# BarGraph.net
KiCad netlist of a schematic drawn in Altium Designer
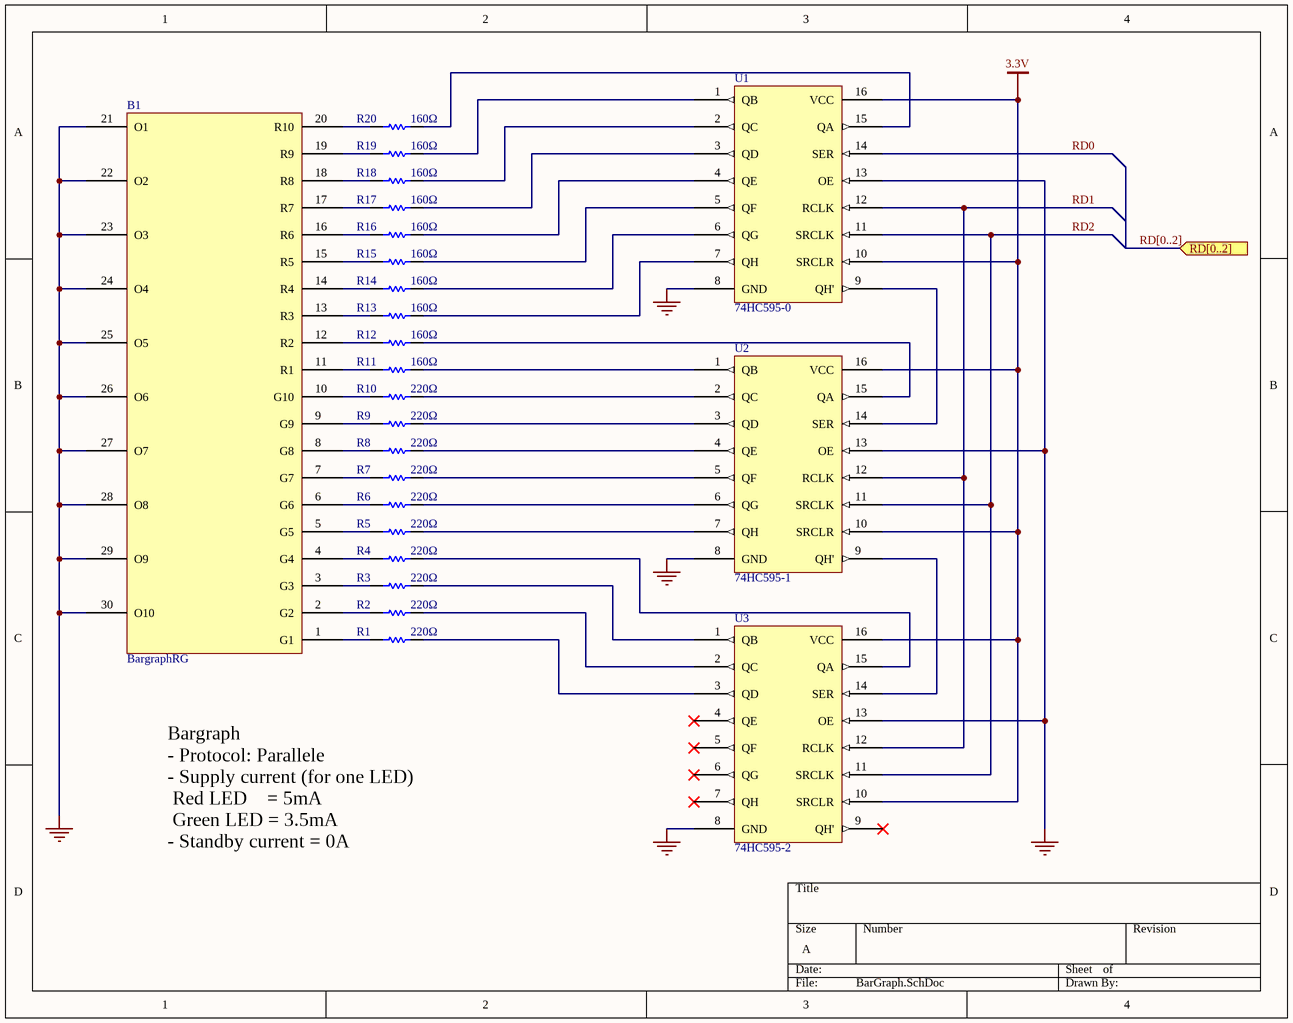
[diagram p0: BarGraph.SchDoc]

(export (version "E")
  (design (tool "Eeschema 10.0.6"))
  (components
    (comp (ref "B1")
      (value "BargraphRG")
      (footprint "BargraphRG")
      (description "Bargraph")
      (fields (field (name "MANUFACTURER") "KINGBRIGHT"))
      (libsource (lib "Electroplant") (part "BargraphRG"))
    )
    (comp (ref "R1")
      (value "220Ω")
      (footprint "R0603")
      (description "Resistor")
      (fields (field (name "PUBLISHER") "Altium Limited"))
      (libsource (lib "Miscellaneous Devices") (part "Res1"))
    )
    (comp (ref "R2")
      (value "220Ω")
      (footprint "R0603")
      (description "Resistor")
      (fields (field (name "PUBLISHER") "Altium Limited"))
      (libsource (lib "Miscellaneous Devices") (part "Res1"))
    )
    (comp (ref "R3")
      (value "220Ω")
      (footprint "R0603")
      (description "Resistor")
      (fields (field (name "PUBLISHER") "Altium Limited"))
      (libsource (lib "Miscellaneous Devices") (part "Res1"))
    )
    (comp (ref "R4")
      (value "220Ω")
      (footprint "R0603")
      (description "Resistor")
      (fields (field (name "PUBLISHER") "Altium Limited"))
      (libsource (lib "Miscellaneous Devices") (part "Res1"))
    )
    (comp (ref "R5")
      (value "220Ω")
      (footprint "R0603")
      (description "Resistor")
      (fields (field (name "PUBLISHER") "Altium Limited"))
      (libsource (lib "Miscellaneous Devices") (part "Res1"))
    )
    (comp (ref "R6")
      (value "220Ω")
      (footprint "R0603")
      (description "Resistor")
      (fields (field (name "PUBLISHER") "Altium Limited"))
      (libsource (lib "Miscellaneous Devices") (part "Res1"))
    )
    (comp (ref "R7")
      (value "220Ω")
      (footprint "R0603")
      (description "Resistor")
      (fields (field (name "PUBLISHER") "Altium Limited"))
      (libsource (lib "Miscellaneous Devices") (part "Res1"))
    )
    (comp (ref "R8")
      (value "220Ω")
      (footprint "R0603")
      (description "Resistor")
      (fields (field (name "PUBLISHER") "Altium Limited"))
      (libsource (lib "Miscellaneous Devices") (part "Res1"))
    )
    (comp (ref "R9")
      (value "220Ω")
      (footprint "R0603")
      (description "Resistor")
      (fields (field (name "PUBLISHER") "Altium Limited"))
      (libsource (lib "Miscellaneous Devices") (part "Res1"))
    )
    (comp (ref "R10")
      (value "220Ω")
      (footprint "R0603")
      (description "Resistor")
      (fields (field (name "PUBLISHER") "Altium Limited"))
      (libsource (lib "Miscellaneous Devices") (part "Res1"))
    )
    (comp (ref "R11")
      (value "160Ω")
      (footprint "R0603")
      (description "Resistor")
      (fields (field (name "PUBLISHER") "Altium Limited"))
      (libsource (lib "Miscellaneous Devices") (part "Res1"))
    )
    (comp (ref "R12")
      (value "160Ω")
      (footprint "R0603")
      (description "Resistor")
      (fields (field (name "PUBLISHER") "Altium Limited"))
      (libsource (lib "Miscellaneous Devices") (part "Res1"))
    )
    (comp (ref "R13")
      (value "160Ω")
      (footprint "R0603")
      (description "Resistor")
      (fields (field (name "PUBLISHER") "Altium Limited"))
      (libsource (lib "Miscellaneous Devices") (part "Res1"))
    )
    (comp (ref "R14")
      (value "160Ω")
      (footprint "R0603")
      (description "Resistor")
      (fields (field (name "PUBLISHER") "Altium Limited"))
      (libsource (lib "Miscellaneous Devices") (part "Res1"))
    )
    (comp (ref "R15")
      (value "160Ω")
      (footprint "R0603")
      (description "Resistor")
      (fields (field (name "PUBLISHER") "Altium Limited"))
      (libsource (lib "Miscellaneous Devices") (part "Res1"))
    )
    (comp (ref "R16")
      (value "160Ω")
      (footprint "R0603")
      (description "Resistor")
      (fields (field (name "PUBLISHER") "Altium Limited"))
      (libsource (lib "Miscellaneous Devices") (part "Res1"))
    )
    (comp (ref "R17")
      (value "160Ω")
      (footprint "R0603")
      (description "Resistor")
      (fields (field (name "PUBLISHER") "Altium Limited"))
      (libsource (lib "Miscellaneous Devices") (part "Res1"))
    )
    (comp (ref "R18")
      (value "160Ω")
      (footprint "R0603")
      (description "Resistor")
      (fields (field (name "PUBLISHER") "Altium Limited"))
      (libsource (lib "Miscellaneous Devices") (part "Res1"))
    )
    (comp (ref "R19")
      (value "160Ω")
      (footprint "R0603")
      (description "Resistor")
      (fields (field (name "PUBLISHER") "Altium Limited"))
      (libsource (lib "Miscellaneous Devices") (part "Res1"))
    )
    (comp (ref "R20")
      (value "160Ω")
      (footprint "R0603")
      (description "Resistor")
      (fields (field (name "PUBLISHER") "Altium Limited"))
      (libsource (lib "Miscellaneous Devices") (part "Res1"))
    )
    (comp (ref "U1")
      (value "74HC595-0")
      (footprint "SN74HC595D")
      (description "ShiftRegister")
      (fields (field (name "MANUFACTURER") "TEXAS INSTRUMENTS"))
      (libsource (lib "Electroplant") (part "74HC595"))
    )
    (comp (ref "U2")
      (value "74HC595-1")
      (footprint "SN74HC595D")
      (description "ShiftRegister")
      (fields (field (name "MANUFACTURER") "TEXAS INSTRUMENTS"))
      (libsource (lib "Electroplant") (part "74HC595"))
    )
    (comp (ref "U3")
      (value "74HC595-2")
      (footprint "SN74HC595D")
      (description "ShiftRegister")
      (fields (field (name "MANUFACTURER") "TEXAS INSTRUMENTS"))
      (libsource (lib "Electroplant") (part "74HC595"))
    )
  )
  (nets
    (net (code "1") (name "/RD0") (class "Default")
      (node (ref "U1") (pin "14") (pinfunction "SER_14") (pintype "input"))
    )
    (net (code "2") (name "/RD1") (class "Default")
      (node (ref "U1") (pin "12") (pinfunction "RCLK_12") (pintype "input"))
      (node (ref "U2") (pin "12") (pinfunction "RCLK_12") (pintype "input"))
      (node (ref "U3") (pin "12") (pinfunction "RCLK_12") (pintype "input"))
    )
    (net (code "3") (name "/RD2") (class "Default")
      (node (ref "U1") (pin "11") (pinfunction "SRCLK_11") (pintype "input"))
      (node (ref "U2") (pin "11") (pinfunction "SRCLK_11") (pintype "input"))
      (node (ref "U3") (pin "11") (pinfunction "SRCLK_11") (pintype "input"))
    )
    (net (code "5") (name "3.3V") (class "Default")
      (node (ref "U1") (pin "10") (pinfunction "SRCLR_10") (pintype "input"))
      (node (ref "U1") (pin "16") (pinfunction "VCC_16") (pintype "power_in"))
      (node (ref "U2") (pin "10") (pinfunction "SRCLR_10") (pintype "input"))
      (node (ref "U2") (pin "16") (pinfunction "VCC_16") (pintype "power_in"))
      (node (ref "U3") (pin "10") (pinfunction "SRCLR_10") (pintype "input"))
      (node (ref "U3") (pin "16") (pinfunction "VCC_16") (pintype "power_in"))
    )
    (net (code "6") (name "GND") (class "Default")
      (node (ref "B1") (pin "21") (pinfunction "O1_21") (pintype "power_in"))
      (node (ref "B1") (pin "22") (pinfunction "O2_22") (pintype "power_in"))
      (node (ref "B1") (pin "23") (pinfunction "O3_23") (pintype "power_in"))
      (node (ref "B1") (pin "24") (pinfunction "O4_24") (pintype "power_in"))
      (node (ref "B1") (pin "25") (pinfunction "O5_25") (pintype "power_in"))
      (node (ref "B1") (pin "26") (pinfunction "O6_26") (pintype "power_in"))
      (node (ref "B1") (pin "27") (pinfunction "O7_27") (pintype "power_in"))
      (node (ref "B1") (pin "28") (pinfunction "O8_28") (pintype "power_in"))
      (node (ref "B1") (pin "29") (pinfunction "O9_29") (pintype "power_in"))
      (node (ref "B1") (pin "30") (pinfunction "O10_30") (pintype "power_in"))
      (node (ref "U1") (pin "13") (pinfunction "OE_13") (pintype "input"))
      (node (ref "U1") (pin "8") (pinfunction "GND_8") (pintype "power_in"))
      (node (ref "U2") (pin "13") (pinfunction "OE_13") (pintype "input"))
      (node (ref "U2") (pin "8") (pinfunction "GND_8") (pintype "power_in"))
      (node (ref "U3") (pin "13") (pinfunction "OE_13") (pintype "input"))
      (node (ref "U3") (pin "8") (pinfunction "GND_8") (pintype "power_in"))
    )
    (net (code "7") (name "Net-(B1-G1)") (class "Default")
      (node (ref "B1") (pin "1") (pinfunction "G1_1") (pintype "power_in"))
      (node (ref "R1") (pin "1") (pinfunction "1_1") (pintype "passive"))
    )
    (net (code "8") (name "Net-(B1-G2)") (class "Default")
      (node (ref "B1") (pin "2") (pinfunction "G2_2") (pintype "power_in"))
      (node (ref "R2") (pin "1") (pinfunction "1_1") (pintype "passive"))
    )
    (net (code "9") (name "Net-(B1-G3)") (class "Default")
      (node (ref "B1") (pin "3") (pinfunction "G3_3") (pintype "power_in"))
      (node (ref "R3") (pin "1") (pinfunction "1_1") (pintype "passive"))
    )
    (net (code "10") (name "Net-(B1-G4)") (class "Default")
      (node (ref "B1") (pin "4") (pinfunction "G4_4") (pintype "power_in"))
      (node (ref "R4") (pin "1") (pinfunction "1_1") (pintype "passive"))
    )
    (net (code "11") (name "Net-(B1-G5)") (class "Default")
      (node (ref "B1") (pin "5") (pinfunction "G5_5") (pintype "power_in"))
      (node (ref "R5") (pin "1") (pinfunction "1_1") (pintype "passive"))
    )
    (net (code "12") (name "Net-(B1-G6)") (class "Default")
      (node (ref "B1") (pin "6") (pinfunction "G6_6") (pintype "power_in"))
      (node (ref "R6") (pin "1") (pinfunction "1_1") (pintype "passive"))
    )
    (net (code "13") (name "Net-(B1-G7)") (class "Default")
      (node (ref "B1") (pin "7") (pinfunction "G7_7") (pintype "power_in"))
      (node (ref "R7") (pin "1") (pinfunction "1_1") (pintype "passive"))
    )
    (net (code "14") (name "Net-(B1-G8)") (class "Default")
      (node (ref "B1") (pin "8") (pinfunction "G8_8") (pintype "power_in"))
      (node (ref "R8") (pin "1") (pinfunction "1_1") (pintype "passive"))
    )
    (net (code "15") (name "Net-(B1-G9)") (class "Default")
      (node (ref "B1") (pin "9") (pinfunction "G9_9") (pintype "power_in"))
      (node (ref "R9") (pin "1") (pinfunction "1_1") (pintype "passive"))
    )
    (net (code "16") (name "Net-(B1-G10)") (class "Default")
      (node (ref "B1") (pin "10") (pinfunction "G10_10") (pintype "power_in"))
      (node (ref "R10") (pin "1") (pinfunction "1_1") (pintype "passive"))
    )
    (net (code "17") (name "Net-(B1-R1)") (class "Default")
      (node (ref "B1") (pin "11") (pinfunction "R1_11") (pintype "power_in"))
      (node (ref "R11") (pin "1") (pinfunction "1_1") (pintype "passive"))
    )
    (net (code "18") (name "Net-(B1-R2)") (class "Default")
      (node (ref "B1") (pin "12") (pinfunction "R2_12") (pintype "power_in"))
      (node (ref "R12") (pin "1") (pinfunction "1_1") (pintype "passive"))
    )
    (net (code "19") (name "Net-(B1-R3)") (class "Default")
      (node (ref "B1") (pin "13") (pinfunction "R3_13") (pintype "power_in"))
      (node (ref "R13") (pin "1") (pinfunction "1_1") (pintype "passive"))
    )
    (net (code "20") (name "Net-(B1-R4)") (class "Default")
      (node (ref "B1") (pin "14") (pinfunction "R4_14") (pintype "power_in"))
      (node (ref "R14") (pin "1") (pinfunction "1_1") (pintype "passive"))
    )
    (net (code "21") (name "Net-(B1-R5)") (class "Default")
      (node (ref "B1") (pin "15") (pinfunction "R5_15") (pintype "power_in"))
      (node (ref "R15") (pin "1") (pinfunction "1_1") (pintype "passive"))
    )
    (net (code "22") (name "Net-(B1-R6)") (class "Default")
      (node (ref "B1") (pin "16") (pinfunction "R6_16") (pintype "power_in"))
      (node (ref "R16") (pin "1") (pinfunction "1_1") (pintype "passive"))
    )
    (net (code "23") (name "Net-(B1-R7)") (class "Default")
      (node (ref "B1") (pin "17") (pinfunction "R7_17") (pintype "power_in"))
      (node (ref "R17") (pin "1") (pinfunction "1_1") (pintype "passive"))
    )
    (net (code "24") (name "Net-(B1-R8)") (class "Default")
      (node (ref "B1") (pin "18") (pinfunction "R8_18") (pintype "power_in"))
      (node (ref "R18") (pin "1") (pinfunction "1_1") (pintype "passive"))
    )
    (net (code "25") (name "Net-(B1-R9)") (class "Default")
      (node (ref "B1") (pin "19") (pinfunction "R9_19") (pintype "power_in"))
      (node (ref "R19") (pin "1") (pinfunction "1_1") (pintype "passive"))
    )
    (net (code "26") (name "Net-(B1-R10)") (class "Default")
      (node (ref "B1") (pin "20") (pinfunction "R10_20") (pintype "power_in"))
      (node (ref "R20") (pin "1") (pinfunction "1_1") (pintype "passive"))
    )
    (net (code "27") (name "Net-(U1-QA)") (class "Default")
      (node (ref "R20") (pin "2") (pinfunction "2_2") (pintype "passive"))
      (node (ref "U1") (pin "15") (pinfunction "QA_15") (pintype "output"))
    )
    (net (code "28") (name "Net-(U1-QB)") (class "Default")
      (node (ref "R19") (pin "2") (pinfunction "2_2") (pintype "passive"))
      (node (ref "U1") (pin "1") (pinfunction "QB_1") (pintype "output"))
    )
    (net (code "29") (name "Net-(U1-QC)") (class "Default")
      (node (ref "R18") (pin "2") (pinfunction "2_2") (pintype "passive"))
      (node (ref "U1") (pin "2") (pinfunction "QC_2") (pintype "output"))
    )
    (net (code "30") (name "Net-(U1-QD)") (class "Default")
      (node (ref "R17") (pin "2") (pinfunction "2_2") (pintype "passive"))
      (node (ref "U1") (pin "3") (pinfunction "QD_3") (pintype "output"))
    )
    (net (code "31") (name "Net-(U1-QE)") (class "Default")
      (node (ref "R16") (pin "2") (pinfunction "2_2") (pintype "passive"))
      (node (ref "U1") (pin "4") (pinfunction "QE_4") (pintype "output"))
    )
    (net (code "32") (name "Net-(U1-QF)") (class "Default")
      (node (ref "R15") (pin "2") (pinfunction "2_2") (pintype "passive"))
      (node (ref "U1") (pin "5") (pinfunction "QF_5") (pintype "output"))
    )
    (net (code "33") (name "Net-(U1-QG)") (class "Default")
      (node (ref "R14") (pin "2") (pinfunction "2_2") (pintype "passive"))
      (node (ref "U1") (pin "6") (pinfunction "QG_6") (pintype "output"))
    )
    (net (code "34") (name "Net-(U1-QH')") (class "Default")
      (node (ref "U1") (pin "9") (pinfunction "QH'_9") (pintype "output"))
      (node (ref "U2") (pin "14") (pinfunction "SER_14") (pintype "input"))
    )
    (net (code "35") (name "Net-(U1-QH)") (class "Default")
      (node (ref "R13") (pin "2") (pinfunction "2_2") (pintype "passive"))
      (node (ref "U1") (pin "7") (pinfunction "QH_7") (pintype "output"))
    )
    (net (code "36") (name "Net-(U2-QA)") (class "Default")
      (node (ref "R12") (pin "2") (pinfunction "2_2") (pintype "passive"))
      (node (ref "U2") (pin "15") (pinfunction "QA_15") (pintype "output"))
    )
    (net (code "37") (name "Net-(U2-QB)") (class "Default")
      (node (ref "R11") (pin "2") (pinfunction "2_2") (pintype "passive"))
      (node (ref "U2") (pin "1") (pinfunction "QB_1") (pintype "output"))
    )
    (net (code "38") (name "Net-(U2-QC)") (class "Default")
      (node (ref "R10") (pin "2") (pinfunction "2_2") (pintype "passive"))
      (node (ref "U2") (pin "2") (pinfunction "QC_2") (pintype "output"))
    )
    (net (code "39") (name "Net-(U2-QD)") (class "Default")
      (node (ref "R9") (pin "2") (pinfunction "2_2") (pintype "passive"))
      (node (ref "U2") (pin "3") (pinfunction "QD_3") (pintype "output"))
    )
    (net (code "40") (name "Net-(U2-QE)") (class "Default")
      (node (ref "R8") (pin "2") (pinfunction "2_2") (pintype "passive"))
      (node (ref "U2") (pin "4") (pinfunction "QE_4") (pintype "output"))
    )
    (net (code "41") (name "Net-(U2-QF)") (class "Default")
      (node (ref "R7") (pin "2") (pinfunction "2_2") (pintype "passive"))
      (node (ref "U2") (pin "5") (pinfunction "QF_5") (pintype "output"))
    )
    (net (code "42") (name "Net-(U2-QG)") (class "Default")
      (node (ref "R6") (pin "2") (pinfunction "2_2") (pintype "passive"))
      (node (ref "U2") (pin "6") (pinfunction "QG_6") (pintype "output"))
    )
    (net (code "43") (name "Net-(U2-QH')") (class "Default")
      (node (ref "U2") (pin "9") (pinfunction "QH'_9") (pintype "output"))
      (node (ref "U3") (pin "14") (pinfunction "SER_14") (pintype "input"))
    )
    (net (code "44") (name "Net-(U2-QH)") (class "Default")
      (node (ref "R5") (pin "2") (pinfunction "2_2") (pintype "passive"))
      (node (ref "U2") (pin "7") (pinfunction "QH_7") (pintype "output"))
    )
    (net (code "45") (name "Net-(U3-QA)") (class "Default")
      (node (ref "R4") (pin "2") (pinfunction "2_2") (pintype "passive"))
      (node (ref "U3") (pin "15") (pinfunction "QA_15") (pintype "output"))
    )
    (net (code "46") (name "Net-(U3-QB)") (class "Default")
      (node (ref "R3") (pin "2") (pinfunction "2_2") (pintype "passive"))
      (node (ref "U3") (pin "1") (pinfunction "QB_1") (pintype "output"))
    )
    (net (code "47") (name "Net-(U3-QC)") (class "Default")
      (node (ref "R2") (pin "2") (pinfunction "2_2") (pintype "passive"))
      (node (ref "U3") (pin "2") (pinfunction "QC_2") (pintype "output"))
    )
    (net (code "48") (name "Net-(U3-QD)") (class "Default")
      (node (ref "R1") (pin "2") (pinfunction "2_2") (pintype "passive"))
      (node (ref "U3") (pin "3") (pinfunction "QD_3") (pintype "output"))
    )
    (net (code "49") (name "unconnected-(U3-QE-Pad4)") (class "Default")
      (node (ref "U3") (pin "4") (pinfunction "QE_4") (pintype "output+no_connect"))
    )
    (net (code "50") (name "unconnected-(U3-QF-Pad5)") (class "Default")
      (node (ref "U3") (pin "5") (pinfunction "QF_5") (pintype "output+no_connect"))
    )
    (net (code "51") (name "unconnected-(U3-QG-Pad6)") (class "Default")
      (node (ref "U3") (pin "6") (pinfunction "QG_6") (pintype "output+no_connect"))
    )
    (net (code "52") (name "unconnected-(U3-QH'-Pad9)") (class "Default")
      (node (ref "U3") (pin "9") (pinfunction "QH'_9") (pintype "output+no_connect"))
    )
    (net (code "53") (name "unconnected-(U3-QH-Pad7)") (class "Default")
      (node (ref "U3") (pin "7") (pinfunction "QH_7") (pintype "output+no_connect"))
    )
  )
)
